# AtxPowerDispatcher.net
KiCad netlist of a schematic drawn in EAGLE
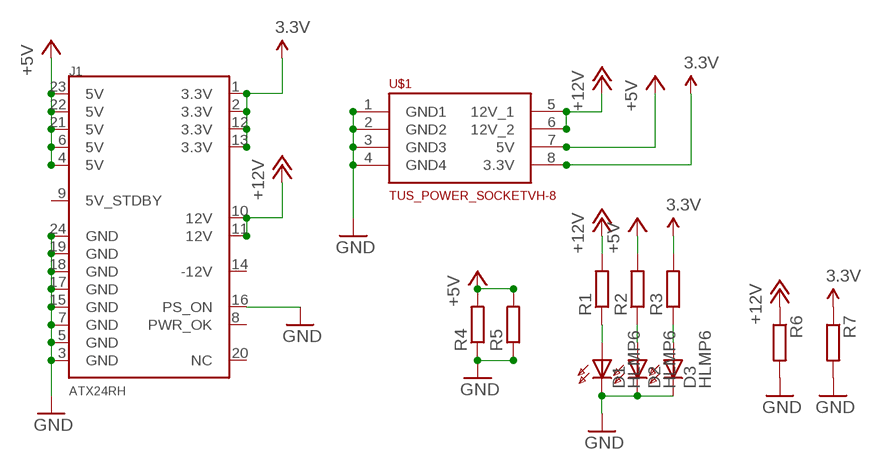
[diagram p0: schematic, sheet 1]

(export (version "E")
  (design (tool "Eeschema 10.0.6"))
  (components
    (comp (ref "D1")
      (value "HLMP6")
      (footprint "eagle-import:HLMP6")
      (fields (field (name "MF") "AGILENT TECHNOLOGIES") (field (name "MPN") "HLMP-6500"))
      (libsource (lib "eagle-import") (part "HLMP6"))
    )
    (comp (ref "D2")
      (value "HLMP6")
      (footprint "eagle-import:HLMP6")
      (fields
        (field (name "MF") "AGILENT TECHNOLOGIES")
        (field (name "MPN") "HLMP-6500")
        (field (name "MF_1") "AGILENT TECHNOLOGIES")
        (field (name "MPN_1") "HLMP-6500")
        (field (name "OC_FARNELL") "1652490")
        (field (name "OC_NEWARK") "40K0088")
      )
      (libsource (lib "eagle-import") (part "HLMP6"))
    )
    (comp (ref "D3")
      (value "HLMP6")
      (footprint "eagle-import:HLMP6")
      (fields
        (field (name "MF") "AGILENT TECHNOLOGIES")
        (field (name "MPN") "HLMP-6500")
        (field (name "MF_1") "AGILENT TECHNOLOGIES")
        (field (name "MPN_1") "HLMP-6500")
        (field (name "OC_FARNELL") "1652490")
        (field (name "OC_NEWARK") "40K0088")
      )
      (libsource (lib "eagle-import") (part "HLMP6"))
    )
    (comp (ref "J1")
      (value "ATX24RH")
      (footprint "eagle-import:ATX24_RIGHT_ANGLE")
      (libsource (lib "eagle-import") (part "ATX24RH"))
    )
    (comp (ref "R1")
      (value "R-EU_0207/7")
      (footprint "eagle-import:0207_7")
      (libsource (lib "eagle-import") (part "R-EU_0207/7"))
    )
    (comp (ref "R2")
      (value "R-EU_0207/7")
      (footprint "eagle-import:0207_7")
      (libsource (lib "eagle-import") (part "R-EU_0207/7"))
    )
    (comp (ref "R3")
      (value "R-EU_0207/7")
      (footprint "eagle-import:0207_7")
      (libsource (lib "eagle-import") (part "R-EU_0207/7"))
    )
    (comp (ref "R4")
      (value "R-EU_0922/22")
      (footprint "eagle-import:0922_22")
      (libsource (lib "eagle-import") (part "resistor_R-EU_0922/22"))
    )
    (comp (ref "R5")
      (value "R-EU_0922/22")
      (footprint "eagle-import:0922_22")
      (libsource (lib "eagle-import") (part "resistor_R-EU_0922/22"))
    )
    (comp (ref "R6")
      (value "R-EU_0414/15")
      (footprint "eagle-import:0414_15")
      (libsource (lib "eagle-import") (part "R-EU_0414/15"))
    )
    (comp (ref "R7")
      (value "R-EU_0414/15")
      (footprint "eagle-import:0414_15")
      (libsource (lib "eagle-import") (part "R-EU_0414/15"))
    )
    (comp (ref "U$1")
      (value "TUS_POWER_SOCKETVH-8")
      (footprint "eagle-import:VH_8")
      (libsource (lib "eagle-import") (part "TUS_POWER_SOCKETVH-8"))
    )
  )
  (nets
    (net (code "1") (name "+5V") (class "Default")
      (node (ref "J1") (pin "21") (pinfunction "5V_21") (pintype "bidirectional"))
      (node (ref "J1") (pin "22") (pinfunction "5V_22") (pintype "bidirectional"))
      (node (ref "J1") (pin "23") (pinfunction "5V_23") (pintype "bidirectional"))
      (node (ref "J1") (pin "4") (pinfunction "5V_4") (pintype "bidirectional"))
      (node (ref "J1") (pin "6") (pinfunction "5V_6") (pintype "bidirectional"))
      (node (ref "R2") (pin "2") (pinfunction "2_2") (pintype "passive"))
      (node (ref "R4") (pin "2") (pinfunction "2_2") (pintype "passive"))
      (node (ref "R5") (pin "2") (pinfunction "2_2") (pintype "passive"))
      (node (ref "U$1") (pin "7") (pinfunction "5V_7") (pintype "power_in"))
    )
    (net (code "2") (name "+12V") (class "Default")
      (node (ref "J1") (pin "10") (pinfunction "12V_10") (pintype "bidirectional"))
      (node (ref "J1") (pin "11") (pinfunction "12V_11") (pintype "bidirectional"))
      (node (ref "R1") (pin "2") (pinfunction "2_2") (pintype "passive"))
      (node (ref "R6") (pin "1") (pinfunction "1_1") (pintype "passive"))
      (node (ref "U$1") (pin "5") (pinfunction "12V_1_5") (pintype "power_in"))
      (node (ref "U$1") (pin "6") (pinfunction "12V_2_6") (pintype "power_in"))
    )
    (net (code "3") (name "3.3V") (class "Default")
      (node (ref "J1") (pin "1") (pinfunction "3.3V_1") (pintype "bidirectional"))
      (node (ref "J1") (pin "12") (pinfunction "3.3V_12") (pintype "bidirectional"))
      (node (ref "J1") (pin "13") (pinfunction "3.3V_13") (pintype "bidirectional"))
      (node (ref "J1") (pin "2") (pinfunction "3.3V_2") (pintype "bidirectional"))
      (node (ref "R3") (pin "2") (pinfunction "2_2") (pintype "passive"))
      (node (ref "R7") (pin "1") (pinfunction "1_1") (pintype "passive"))
      (node (ref "U$1") (pin "8") (pinfunction "3.3V_8") (pintype "power_in"))
    )
    (net (code "4") (name "GND") (class "Default")
      (node (ref "D1") (pin "K") (pinfunction "K_K") (pintype "passive"))
      (node (ref "D2") (pin "K") (pinfunction "K_K") (pintype "passive"))
      (node (ref "D3") (pin "K") (pinfunction "K_K") (pintype "passive"))
      (node (ref "J1") (pin "15") (pinfunction "GND_15") (pintype "bidirectional"))
      (node (ref "J1") (pin "16") (pinfunction "PS_ON_16") (pintype "bidirectional"))
      (node (ref "J1") (pin "17") (pinfunction "GND_17") (pintype "bidirectional"))
      (node (ref "J1") (pin "18") (pinfunction "GND_18") (pintype "bidirectional"))
      (node (ref "J1") (pin "19") (pinfunction "GND_19") (pintype "bidirectional"))
      (node (ref "J1") (pin "24") (pinfunction "GND_24") (pintype "bidirectional"))
      (node (ref "J1") (pin "3") (pinfunction "GND_3") (pintype "bidirectional"))
      (node (ref "J1") (pin "5") (pinfunction "GND_5") (pintype "bidirectional"))
      (node (ref "J1") (pin "7") (pinfunction "GND_7") (pintype "bidirectional"))
      (node (ref "R4") (pin "1") (pinfunction "1_1") (pintype "passive"))
      (node (ref "R5") (pin "1") (pinfunction "1_1") (pintype "passive"))
      (node (ref "R6") (pin "2") (pinfunction "2_2") (pintype "passive"))
      (node (ref "R7") (pin "2") (pinfunction "2_2") (pintype "passive"))
      (node (ref "U$1") (pin "1") (pinfunction "GND1_1") (pintype "power_in"))
      (node (ref "U$1") (pin "2") (pinfunction "GND2_2") (pintype "power_in"))
      (node (ref "U$1") (pin "3") (pinfunction "GND3_3") (pintype "power_in"))
      (node (ref "U$1") (pin "4") (pinfunction "GND4_4") (pintype "power_in"))
    )
    (net (code "5") (name "Net-(D1-PadA)") (class "Default")
      (node (ref "D1") (pin "A") (pinfunction "A_A") (pintype "passive"))
      (node (ref "R1") (pin "1") (pinfunction "1_1") (pintype "passive"))
    )
    (net (code "6") (name "Net-(D2-PadA)") (class "Default")
      (node (ref "D2") (pin "A") (pinfunction "A_A") (pintype "passive"))
      (node (ref "R2") (pin "1") (pinfunction "1_1") (pintype "passive"))
    )
    (net (code "7") (name "Net-(D3-PadA)") (class "Default")
      (node (ref "D3") (pin "A") (pinfunction "A_A") (pintype "passive"))
      (node (ref "R3") (pin "1") (pinfunction "1_1") (pintype "passive"))
    )
    (net (code "8") (name "unconnected-(J1--12V-Pad14)") (class "Default")
      (node (ref "J1") (pin "14") (pinfunction "-12V_14") (pintype "bidirectional"))
    )
    (net (code "9") (name "unconnected-(J1-5V_STDBY-Pad9)") (class "Default")
      (node (ref "J1") (pin "9") (pinfunction "5V_STDBY_9") (pintype "bidirectional"))
    )
    (net (code "10") (name "unconnected-(J1-NC-Pad20)") (class "Default")
      (node (ref "J1") (pin "20") (pinfunction "NC_20") (pintype "bidirectional"))
    )
    (net (code "11") (name "unconnected-(J1-PWR_OK-Pad8)") (class "Default")
      (node (ref "J1") (pin "8") (pinfunction "PWR_OK_8") (pintype "bidirectional"))
    )
  )
)
